# USB_TO_UART.net
KiCad netlist of a schematic drawn in Altium Designer
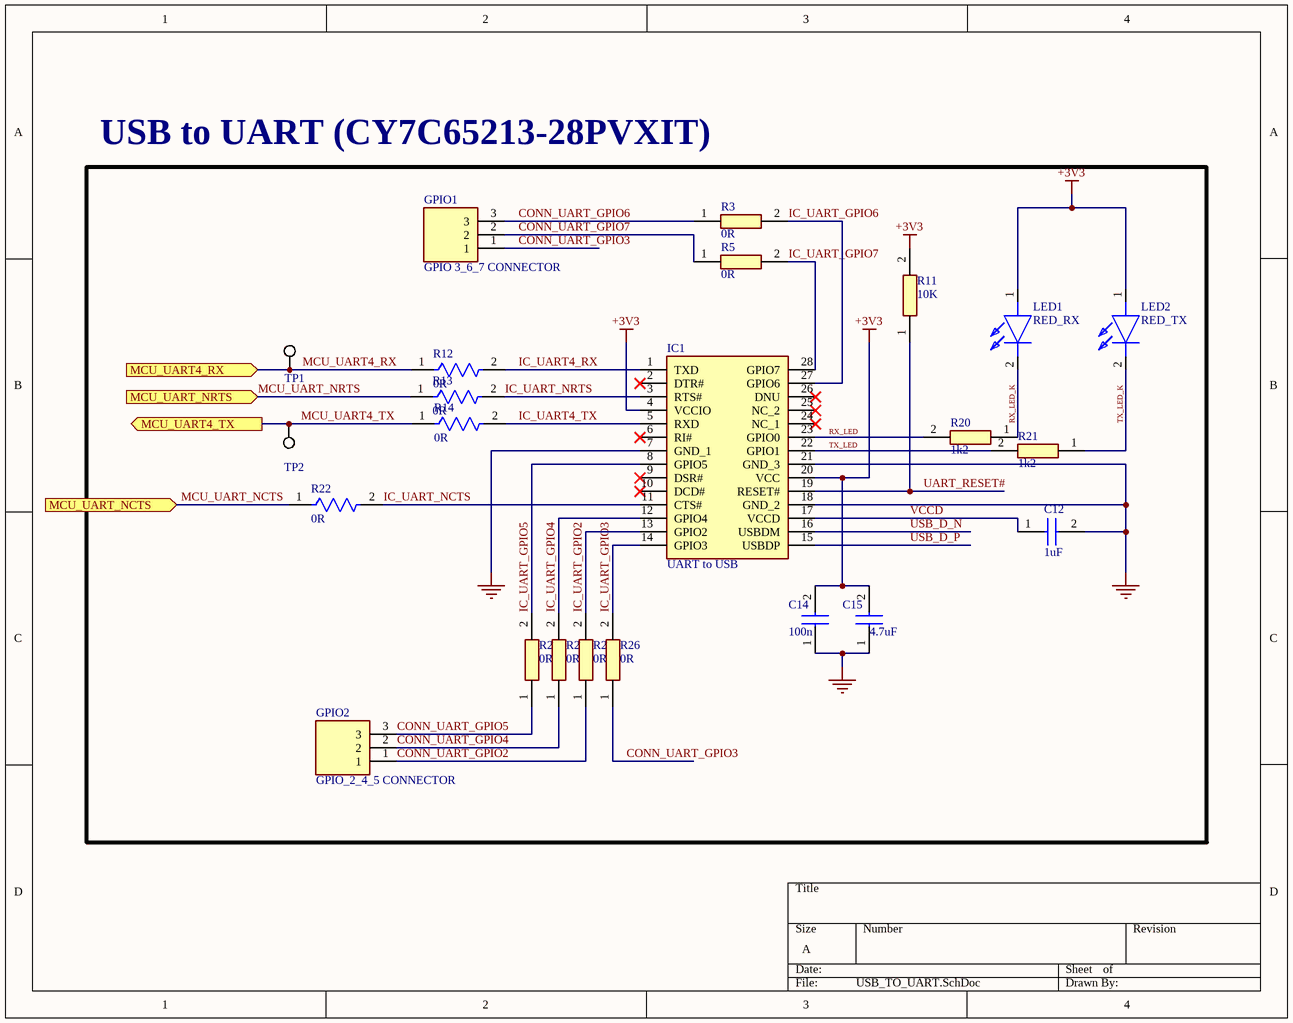
[diagram p0: USB_TO_UART.SchDoc]

(export (version "E")
  (design (tool "Eeschema 10.0.6"))
  (components
    (comp (ref "C12")
      (value "1uF")
      (footprint "SamacSys:CAPC1608X90N")
      (description "Capacitor")
      (fields
        (field (name "MANUFACTURER_PART_NUMBER") "CL10A105KA8NFNC")
        (field (name "MOUSER PART NUMBER") "187-CL10A105KA8NFNC")
      )
      (libsource (lib "SamacSys") (part "CL10A105KA8NFNC"))
    )
    (comp (ref "C14")
      (value "100n")
      (footprint "SamacSys:CAPC1608X95N")
      (description "Capacitor")
      (fields
        (field (name "MANUFACTURER_PART_NUMBER") "C0603C104J4RAC")
        (field (name "MOUSER PART NUMBER") "80-C0603C104J4RAC")
      )
      (libsource (lib "SamacSys") (part "C0603C104J4RAC"))
    )
    (comp (ref "C15")
      (value "4.7uF")
      (footprint "SamacSys:CAPC1608X95N")
      (description "Capacitor")
      (fields
        (field (name "MANUFACTURER_PART_NUMBER") "C0603C104J4RAC")
        (field (name "MOUSER PART NUMBER") "80-C0603C104J4RAC")
      )
      (libsource (lib "SamacSys") (part "C0603C104J4RAC"))
    )
    (comp (ref "GPIO1")
      (value "GPIO 3_6_7 CONNECTOR")
      (footprint "SamacSys:HDRV3W64P0X254_1X3_762X254X864P")
      (description "Connector")
      (fields
        (field (name "MANUFACTURER_PART_NUMBER") "M20-9990345")
        (field (name "MOUSER PART NUMBER") "855-M20-9990345")
      )
      (libsource (lib "SamacSys") (part "M20-9990345"))
    )
    (comp (ref "GPIO2")
      (value "GPIO_2_4_5 CONNECTOR")
      (footprint "SamacSys:HDRV3W64P0X254_1X3_762X254X864P")
      (description "Connector")
      (fields
        (field (name "MANUFACTURER_PART_NUMBER") "M20-9990345")
        (field (name "MOUSER PART NUMBER") "855-M20-9990345")
      )
      (libsource (lib "SamacSys") (part "M20-9990345"))
    )
    (comp (ref "IC1")
      (value "UART to USB")
      (footprint "SamacSys:SOP65P780X200-28N")
      (description "Integrated Circuit")
      (fields
        (field (name "MANUFACTURER_PART_NUMBER") "CY7C65213-28PVXIT")
        (field (name "MOUSER PART NUMBER") "727-CY7C6521328PVXIT")
      )
      (libsource (lib "*") (part "CY7C65213-28PVXIT"))
    )
    (comp (ref "LED1")
      (value "RED_RX")
      (footprint "SamacSys:APT2012SECKJ3PRV")
      (description "LED")
      (fields
        (field (name "MANUFACTURER_PART_NUMBER") "APT2012SECK/J3-PRV")
        (field (name "MOUSER PART NUMBER") "604-APT2012SECKJ3PRV")
      )
      (libsource (lib "*") (part "APT2012SECK_J3-PRV"))
    )
    (comp (ref "LED2")
      (value "RED_TX")
      (footprint "SamacSys:APT2012SECKJ3PRV")
      (description "LED")
      (fields
        (field (name "MANUFACTURER_PART_NUMBER") "APT2012SECK/J3-PRV")
        (field (name "MOUSER PART NUMBER") "604-APT2012SECKJ3PRV")
      )
      (libsource (lib "*") (part "APT2012SECK_J3-PRV"))
    )
    (comp (ref "R3")
      (value "0R")
      (footprint "SamacSys:RESC1608X55N")
      (description "Resistor")
      (fields
        (field (name "MANUFACTURER_PART_NUMBER") "RK73B1JTTD103J")
        (field (name "MOUSER PART NUMBER") "660-RK73B1JTTD103J")
      )
      (libsource (lib "") (part "RK73B1JTTD103J_1"))
    )
    (comp (ref "R5")
      (value "0R")
      (footprint "SamacSys:RESC1608X55N")
      (description "Resistor")
      (fields
        (field (name "MANUFACTURER_PART_NUMBER") "RK73B1JTTD103J")
        (field (name "MOUSER PART NUMBER") "660-RK73B1JTTD103J")
      )
      (libsource (lib "") (part "RK73B1JTTD103J_1"))
    )
    (comp (ref "R11")
      (value "10K")
      (footprint "SamacSys:RESC1608X55N")
      (description "Resistor")
      (fields
        (field (name "MANUFACTURER_PART_NUMBER") "RK73B1JTTD103J")
        (field (name "MOUSER PART NUMBER") "660-RK73B1JTTD103J")
      )
      (libsource (lib "*") (part "RK73B1JTTD103J"))
    )
    (comp (ref "R12")
      (value "0R")
      (footprint "FP-ERJ-3GEY0R00V-MFG")
      (description "RES SMD 0 OHM JUMPER 1/10W 0603")
      (fields (field (name "TOLERANCE") "5%") (field (name "MANUFACTURER PART NUMBER") "ERJ-3GEY0R00V"))
      (libsource (lib "Altium Content Vault") (part "1029c3af85768c4190bb7ad29bc67b5"))
    )
    (comp (ref "R13")
      (value "0R")
      (footprint "FP-ERJ-3GEY0R00V-MFG")
      (description "RES SMD 0 OHM JUMPER 1/10W 0603")
      (fields (field (name "TOLERANCE") "5%") (field (name "MANUFACTURER PART NUMBER") "ERJ-3GEY0R00V"))
      (libsource (lib "Altium Content Vault") (part "1029c3af85768c4190bb7ad29bc67b5"))
    )
    (comp (ref "R14")
      (value "0R")
      (footprint "FP-ERJ-3GEY0R00V-MFG")
      (description "RES SMD 0 OHM JUMPER 1/10W 0603")
      (fields (field (name "TOLERANCE") "5%") (field (name "MANUFACTURER PART NUMBER") "ERJ-3GEY0R00V"))
      (libsource (lib "Altium Content Vault") (part "1029c3af85768c4190bb7ad29bc67b5"))
    )
    (comp (ref "R20")
      (value "1k2")
      (footprint "SamacSys:RESC1608X55N")
      (description "Resistor")
      (fields
        (field (name "MANUFACTURER_PART_NUMBER") "RK73B1JTTD103J")
        (field (name "MOUSER PART NUMBER") "660-RK73B1JTTD103J")
      )
      (libsource (lib "") (part "RK73B1JTTD103J_2"))
    )
    (comp (ref "R21")
      (value "1k2")
      (footprint "SamacSys:RESC1608X55N")
      (description "Resistor")
      (fields
        (field (name "MANUFACTURER_PART_NUMBER") "RK73B1JTTD103J")
        (field (name "MOUSER PART NUMBER") "660-RK73B1JTTD103J")
      )
      (libsource (lib "") (part "RK73B1JTTD103J_2"))
    )
    (comp (ref "R22")
      (value "0R")
      (footprint "FP-ERJ-3GEY0R00V-MFG")
      (description "RES SMD 0 OHM JUMPER 1/10W 0603")
      (fields (field (name "TOLERANCE") "5%") (field (name "MANUFACTURER PART NUMBER") "ERJ-3GEY0R00V"))
      (libsource (lib "Altium Content Vault") (part "1029c3af85768c4190bb7ad29bc67b5"))
    )
    (comp (ref "R23")
      (value "0R")
      (footprint "SamacSys:RESC1608X55N")
      (description "Resistor")
      (fields
        (field (name "MANUFACTURER_PART_NUMBER") "RK73B1JTTD103J")
        (field (name "MOUSER PART NUMBER") "660-RK73B1JTTD103J")
      )
      (libsource (lib "*") (part "RK73B1JTTD103J"))
    )
    (comp (ref "R24")
      (value "0R")
      (footprint "SamacSys:RESC1608X55N")
      (description "Resistor")
      (fields
        (field (name "MANUFACTURER_PART_NUMBER") "RK73B1JTTD103J")
        (field (name "MOUSER PART NUMBER") "660-RK73B1JTTD103J")
      )
      (libsource (lib "*") (part "RK73B1JTTD103J"))
    )
    (comp (ref "R25")
      (value "0R")
      (footprint "SamacSys:RESC1608X55N")
      (description "Resistor")
      (fields
        (field (name "MANUFACTURER_PART_NUMBER") "RK73B1JTTD103J")
        (field (name "MOUSER PART NUMBER") "660-RK73B1JTTD103J")
      )
      (libsource (lib "*") (part "RK73B1JTTD103J"))
    )
    (comp (ref "R26")
      (value "0R")
      (footprint "SamacSys:RESC1608X55N")
      (description "Resistor")
      (fields
        (field (name "MANUFACTURER_PART_NUMBER") "RK73B1JTTD103J")
        (field (name "MOUSER PART NUMBER") "660-RK73B1JTTD103J")
      )
      (libsource (lib "*") (part "RK73B1JTTD103J"))
    )
    (comp (ref "TP1")
      (value "5019")
      (footprint "KSTN-5019_V")
      (description "Test Point, 1 Position SMD, RoHS, Tape and Reel")
      (libsource (lib "Altium Content Vault") (part "TESTPOINT_WHITE"))
    )
    (comp (ref "TP2")
      (value "5019")
      (footprint "KSTN-5019_V")
      (description "Test Point, 1 Position SMD, RoHS, Tape and Reel")
      (libsource (lib "Altium Content Vault") (part "TESTPOINT_WHITE"))
    )
  )
  (nets
    (net (code "1") (name "+3V3") (class "Default")
      (node (ref "C14") (pin "2") (pinfunction "2_2") (pintype "passive"))
      (node (ref "C15") (pin "2") (pinfunction "2_2") (pintype "passive"))
      (node (ref "IC1") (pin "20") (pinfunction "VCC_20") (pintype "passive"))
      (node (ref "IC1") (pin "4") (pinfunction "VCCIO_4") (pintype "passive"))
      (node (ref "LED1") (pin "1") (pinfunction "A_1") (pintype "passive"))
      (node (ref "LED2") (pin "1") (pinfunction "A_1") (pintype "passive"))
      (node (ref "R11") (pin "2") (pinfunction "2_2") (pintype "passive"))
    )
    (net (code "2") (name "/CONN_UART_GPIO2") (class "Default")
      (node (ref "GPIO2") (pin "1") (pinfunction "1_1") (pintype "passive"))
      (node (ref "R25") (pin "1") (pinfunction "1_1") (pintype "passive"))
    )
    (net (code "3") (name "/CONN_UART_GPIO3") (class "Default")
      (node (ref "GPIO1") (pin "1") (pinfunction "1_1") (pintype "passive"))
      (node (ref "R26") (pin "1") (pinfunction "1_1") (pintype "passive"))
    )
    (net (code "4") (name "/CONN_UART_GPIO4") (class "Default")
      (node (ref "GPIO2") (pin "2") (pinfunction "2_2") (pintype "passive"))
      (node (ref "R24") (pin "1") (pinfunction "1_1") (pintype "passive"))
    )
    (net (code "5") (name "/CONN_UART_GPIO5") (class "Default")
      (node (ref "GPIO2") (pin "3") (pinfunction "3_3") (pintype "passive"))
      (node (ref "R23") (pin "1") (pinfunction "1_1") (pintype "passive"))
    )
    (net (code "6") (name "/CONN_UART_GPIO6") (class "Default")
      (node (ref "GPIO1") (pin "3") (pinfunction "3_3") (pintype "passive"))
      (node (ref "R3") (pin "1") (pinfunction "1_1") (pintype "passive"))
    )
    (net (code "7") (name "/CONN_UART_GPIO7") (class "Default")
      (node (ref "GPIO1") (pin "2") (pinfunction "2_2") (pintype "passive"))
      (node (ref "R5") (pin "1") (pinfunction "1_1") (pintype "passive"))
    )
    (net (code "8") (name "/IC_UART4_RX") (class "Default")
      (node (ref "IC1") (pin "1") (pinfunction "TXD_1") (pintype "passive"))
      (node (ref "R12") (pin "2") (pinfunction "2_2") (pintype "passive"))
    )
    (net (code "9") (name "/IC_UART4_TX") (class "Default")
      (node (ref "IC1") (pin "5") (pinfunction "RXD_5") (pintype "passive"))
      (node (ref "R14") (pin "2") (pinfunction "2_2") (pintype "passive"))
    )
    (net (code "10") (name "/IC_UART_GPIO2") (class "Default")
      (node (ref "IC1") (pin "13") (pinfunction "GPIO2_13") (pintype "passive"))
      (node (ref "R25") (pin "2") (pinfunction "2_2") (pintype "passive"))
    )
    (net (code "11") (name "/IC_UART_GPIO3") (class "Default")
      (node (ref "IC1") (pin "14") (pinfunction "GPIO3_14") (pintype "passive"))
      (node (ref "R26") (pin "2") (pinfunction "2_2") (pintype "passive"))
    )
    (net (code "12") (name "/IC_UART_GPIO4") (class "Default")
      (node (ref "IC1") (pin "12") (pinfunction "GPIO4_12") (pintype "passive"))
      (node (ref "R24") (pin "2") (pinfunction "2_2") (pintype "passive"))
    )
    (net (code "13") (name "/IC_UART_GPIO5") (class "Default")
      (node (ref "IC1") (pin "8") (pinfunction "GPIO5_8") (pintype "passive"))
      (node (ref "R23") (pin "2") (pinfunction "2_2") (pintype "passive"))
    )
    (net (code "14") (name "/IC_UART_GPIO6") (class "Default")
      (node (ref "IC1") (pin "27") (pinfunction "GPIO6_27") (pintype "passive"))
      (node (ref "R3") (pin "2") (pinfunction "2_2") (pintype "passive"))
    )
    (net (code "15") (name "/IC_UART_GPIO7") (class "Default")
      (node (ref "IC1") (pin "28") (pinfunction "GPIO7_28") (pintype "passive"))
      (node (ref "R5") (pin "2") (pinfunction "2_2") (pintype "passive"))
    )
    (net (code "16") (name "/IC_UART_NCTS") (class "Default")
      (node (ref "IC1") (pin "11") (pinfunction "CTS#_11") (pintype "passive"))
      (node (ref "R22") (pin "2") (pinfunction "2_2") (pintype "passive"))
    )
    (net (code "17") (name "/IC_UART_NRTS") (class "Default")
      (node (ref "IC1") (pin "3") (pinfunction "RTS#_3") (pintype "passive"))
      (node (ref "R13") (pin "2") (pinfunction "2_2") (pintype "passive"))
    )
    (net (code "18") (name "/MCU_UART4_RX") (class "Default")
      (node (ref "R12") (pin "1") (pinfunction "1_1") (pintype "passive"))
      (node (ref "TP1") (pin "1") (pinfunction "1_1") (pintype "passive"))
    )
    (net (code "19") (name "/MCU_UART4_TX") (class "Default")
      (node (ref "R14") (pin "1") (pinfunction "1_1") (pintype "passive"))
      (node (ref "TP2") (pin "1") (pinfunction "1_1") (pintype "passive"))
    )
    (net (code "20") (name "/MCU_UART_NCTS") (class "Default")
      (node (ref "R22") (pin "1") (pinfunction "1_1") (pintype "passive"))
    )
    (net (code "21") (name "/MCU_UART_NRTS") (class "Default")
      (node (ref "R13") (pin "1") (pinfunction "1_1") (pintype "passive"))
    )
    (net (code "22") (name "/RX_LED") (class "Default")
      (node (ref "IC1") (pin "23") (pinfunction "GPIO0_23") (pintype "passive"))
      (node (ref "R20") (pin "2") (pinfunction "2_2") (pintype "passive"))
    )
    (net (code "23") (name "/RX_LED_K") (class "Default")
      (node (ref "LED1") (pin "2") (pinfunction "K_2") (pintype "passive"))
      (node (ref "R20") (pin "1") (pinfunction "1_1") (pintype "passive"))
    )
    (net (code "24") (name "/TX_LED") (class "Default")
      (node (ref "IC1") (pin "22") (pinfunction "GPIO1_22") (pintype "passive"))
      (node (ref "R21") (pin "2") (pinfunction "2_2") (pintype "passive"))
    )
    (net (code "25") (name "/TX_LED_K") (class "Default")
      (node (ref "LED2") (pin "2") (pinfunction "K_2") (pintype "passive"))
      (node (ref "R21") (pin "1") (pinfunction "1_1") (pintype "passive"))
    )
    (net (code "26") (name "/UART_RESET#") (class "Default")
      (node (ref "IC1") (pin "19") (pinfunction "RESET#_19") (pintype "passive"))
      (node (ref "R11") (pin "1") (pinfunction "1_1") (pintype "passive"))
    )
    (net (code "27") (name "/USB_D_N") (class "Default")
      (node (ref "IC1") (pin "16") (pinfunction "USBDM_16") (pintype "passive"))
    )
    (net (code "28") (name "/USB_D_P") (class "Default")
      (node (ref "IC1") (pin "15") (pinfunction "USBDP_15") (pintype "passive"))
    )
    (net (code "29") (name "/VCCD") (class "Default")
      (node (ref "C12") (pin "1") (pinfunction "1_1") (pintype "passive"))
      (node (ref "IC1") (pin "17") (pinfunction "VCCD_17") (pintype "passive"))
    )
    (net (code "30") (name "GND") (class "Default")
      (node (ref "C12") (pin "2") (pinfunction "2_2") (pintype "passive"))
      (node (ref "C14") (pin "1") (pinfunction "1_1") (pintype "passive"))
      (node (ref "C15") (pin "1") (pinfunction "1_1") (pintype "passive"))
      (node (ref "IC1") (pin "18") (pinfunction "GND_2_18") (pintype "passive"))
      (node (ref "IC1") (pin "21") (pinfunction "GND_3_21") (pintype "passive"))
      (node (ref "IC1") (pin "7") (pinfunction "GND_1_7") (pintype "passive"))
    )
    (net (code "31") (name "unconnected-(IC1-DCD#-Pad10)") (class "Default")
      (node (ref "IC1") (pin "10") (pinfunction "DCD#_10") (pintype "passive+no_connect"))
    )
    (net (code "32") (name "unconnected-(IC1-DNU-Pad26)") (class "Default")
      (node (ref "IC1") (pin "26") (pinfunction "DNU_26") (pintype "passive+no_connect"))
    )
    (net (code "33") (name "unconnected-(IC1-DSR#-Pad9)") (class "Default")
      (node (ref "IC1") (pin "9") (pinfunction "DSR#_9") (pintype "passive+no_connect"))
    )
    (net (code "34") (name "unconnected-(IC1-DTR#-Pad2)") (class "Default")
      (node (ref "IC1") (pin "2") (pinfunction "DTR#_2") (pintype "passive+no_connect"))
    )
    (net (code "35") (name "unconnected-(IC1-NC_1-Pad24)") (class "Default")
      (node (ref "IC1") (pin "24") (pinfunction "NC_1_24") (pintype "passive+no_connect"))
    )
    (net (code "36") (name "unconnected-(IC1-NC_2-Pad25)") (class "Default")
      (node (ref "IC1") (pin "25") (pinfunction "NC_2_25") (pintype "passive+no_connect"))
    )
    (net (code "37") (name "unconnected-(IC1-RI#-Pad6)") (class "Default")
      (node (ref "IC1") (pin "6") (pinfunction "RI#_6") (pintype "passive+no_connect"))
    )
  )
)
